# rpr-v1.net
KiCad netlist of a schematic drawn in EAGLE
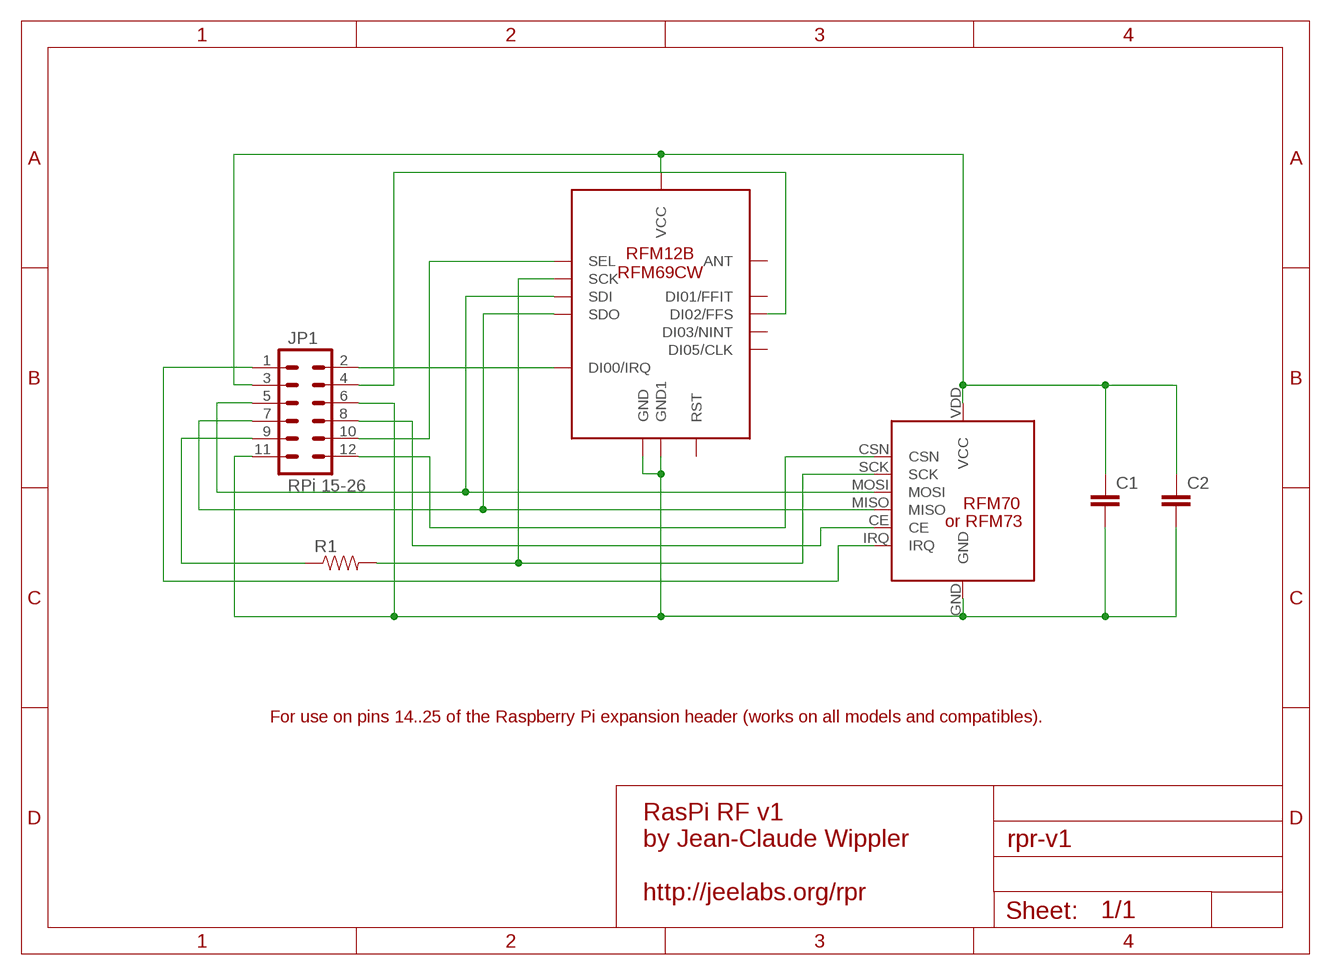
[diagram p0: schematic, sheet 1]

(export (version "E")
  (design (tool "Eeschema 10.0.6"))
  (components
    (comp (ref "C1")
      (value "CAP0805")
      (footprint "eagle-import:0805")
      (libsource (lib "eagle-import") (part "CAP0805"))
    )
    (comp (ref "C2")
      (value "CAP0805")
      (footprint "eagle-import:0805")
      (libsource (lib "eagle-import") (part "CAP0805"))
    )
    (comp (ref "JP1")
      (value "RPi 15-26")
      (footprint "eagle-import:2X6")
      (libsource (lib "eagle-import") (part "M06X2PTH_FEMALE"))
    )
    (comp (ref "R1")
      (value "RESISTOR0603-RES")
      (footprint "eagle-import:0603-RES")
      (libsource (lib "eagle-import") (part "RESISTOR0603-RES"))
    )
    (comp (ref "RFM12B/69CW")
      (value "RFM12B/69CW")
      (footprint "eagle-import:RFM12B_69CW")
      (libsource (lib "eagle-import") (part "RFM12B/69CW"))
    )
    (comp (ref "U$1")
      (value "RFM70")
      (footprint "eagle-import:RFM70")
      (libsource (lib "eagle-import") (part "RFM70"))
    )
  )
  (nets
    (net (code "1") (name "Net-(C1-Pad2)") (class "Default")
      (node (ref "C1") (pin "2") (pinfunction "2_2") (pintype "passive"))
      (node (ref "C2") (pin "2") (pinfunction "2_2") (pintype "passive"))
      (node (ref "JP1") (pin "11") (pinfunction "11_11") (pintype "passive"))
      (node (ref "JP1") (pin "6") (pinfunction "6_6") (pintype "passive"))
      (node (ref "RFM12B/69CW") (pin "GND") (pinfunction "GND_GND") (pintype "power_in"))
      (node (ref "RFM12B/69CW") (pin "GND1") (pinfunction "GND1_GND1") (pintype "power_in"))
      (node (ref "U$1") (pin "GND") (pinfunction "GND_GND") (pintype "power_in"))
    )
    (net (code "2") (name "Net-(JP1-Pad1)") (class "Default")
      (node (ref "JP1") (pin "1") (pinfunction "1_1") (pintype "passive"))
      (node (ref "U$1") (pin "IRQ") (pinfunction "IRQ_IRQ") (pintype "open_collector"))
    )
    (net (code "3") (name "Net-(JP1-Pad5)") (class "Default")
      (node (ref "JP1") (pin "5") (pinfunction "5_5") (pintype "passive"))
      (node (ref "RFM12B/69CW") (pin "SDI") (pinfunction "SDI_SDI") (pintype "input"))
      (node (ref "U$1") (pin "MOSI") (pinfunction "MOSI_MOSI") (pintype "input"))
    )
    (net (code "4") (name "Net-(JP1-Pad7)") (class "Default")
      (node (ref "JP1") (pin "7") (pinfunction "7_7") (pintype "passive"))
      (node (ref "RFM12B/69CW") (pin "SDO") (pinfunction "SDO_SDO") (pintype "output"))
      (node (ref "U$1") (pin "MISO") (pinfunction "MISO_MISO") (pintype "output"))
    )
    (net (code "5") (name "Net-(JP1-Pad8)") (class "Default")
      (node (ref "JP1") (pin "8") (pinfunction "8_8") (pintype "passive"))
      (node (ref "U$1") (pin "CE") (pinfunction "CE_CE") (pintype "bidirectional"))
    )
    (net (code "6") (name "Net-(JP1-Pad9)") (class "Default")
      (node (ref "JP1") (pin "9") (pinfunction "9_9") (pintype "passive"))
      (node (ref "R1") (pin "1") (pinfunction "1_1") (pintype "passive"))
    )
    (net (code "7") (name "Net-(JP1-Pad10)") (class "Default")
      (node (ref "JP1") (pin "10") (pinfunction "10_10") (pintype "passive"))
      (node (ref "RFM12B/69CW") (pin "SEL") (pinfunction "SEL_SEL") (pintype "input"))
    )
    (net (code "8") (name "Net-(JP1-Pad12)") (class "Default")
      (node (ref "JP1") (pin "12") (pinfunction "12_12") (pintype "passive"))
      (node (ref "U$1") (pin "CSN") (pinfunction "CSN_CSN") (pintype "input"))
    )
    (net (code "9") (name "Net-(R1-Pad2)") (class "Default")
      (node (ref "R1") (pin "2") (pinfunction "2_2") (pintype "passive"))
      (node (ref "RFM12B/69CW") (pin "SCK") (pinfunction "SCK_SCK") (pintype "input"))
      (node (ref "U$1") (pin "SCK") (pinfunction "SCK_SCK") (pintype "input"))
    )
    (net (code "10") (name "Net-(RFM12B/69CW-DI00{slash}IRQ)") (class "Default")
      (node (ref "JP1") (pin "2") (pinfunction "2_2") (pintype "passive"))
      (node (ref "RFM12B/69CW") (pin "IRQ") (pinfunction "DI00/IRQ_IRQ") (pintype "open_collector"))
    )
    (net (code "11") (name "Net-(RFM12B/69CW-DI02{slash}FFS)") (class "Default")
      (node (ref "JP1") (pin "4") (pinfunction "4_4") (pintype "passive"))
      (node (ref "RFM12B/69CW") (pin "FFS") (pinfunction "DI02/FFS_FFS") (pintype "bidirectional"))
    )
    (net (code "12") (name "Net-(RFM12B/69CW-VCC)") (class "Default")
      (node (ref "C1") (pin "1") (pinfunction "1_1") (pintype "passive"))
      (node (ref "C2") (pin "1") (pinfunction "1_1") (pintype "passive"))
      (node (ref "JP1") (pin "3") (pinfunction "3_3") (pintype "passive"))
      (node (ref "RFM12B/69CW") (pin "VDD") (pinfunction "VCC_VDD") (pintype "power_in"))
      (node (ref "U$1") (pin "VDD") (pinfunction "VCC_VDD") (pintype "power_in"))
    )
    (net (code "13") (name "unconnected-(RFM12B/69CW-DI01{slash}FFIT-PadFFIT)") (class "Default")
      (node (ref "RFM12B/69CW") (pin "FFIT") (pinfunction "DI01/FFIT_FFIT") (pintype "passive"))
    )
    (net (code "14") (name "unconnected-(RFM12B/69CW-DI03{slash}NINT-PadNINT)") (class "Default")
      (node (ref "RFM12B/69CW") (pin "NINT") (pinfunction "DI03/NINT_NINT") (pintype "passive"))
    )
    (net (code "15") (name "unconnected-(RFM12B/69CW-DI05{slash}CLK-PadCLK)") (class "Default")
      (node (ref "RFM12B/69CW") (pin "CLK") (pinfunction "DI05/CLK_CLK") (pintype "passive"))
    )
    (net (code "16") (name "unconnected-(RFM12B/69CW-PadANT)") (class "Default")
      (node (ref "RFM12B/69CW") (pin "ANT") (pinfunction "ANT_ANT") (pintype "passive"))
    )
    (net (code "17") (name "unconnected-(RFM12B/69CW-PadRST)") (class "Default")
      (node (ref "RFM12B/69CW") (pin "RST") (pinfunction "RST_RST") (pintype "open_collector"))
    )
  )
)
